# controller.net
KiCad netlist of a schematic drawn in Altium Designer
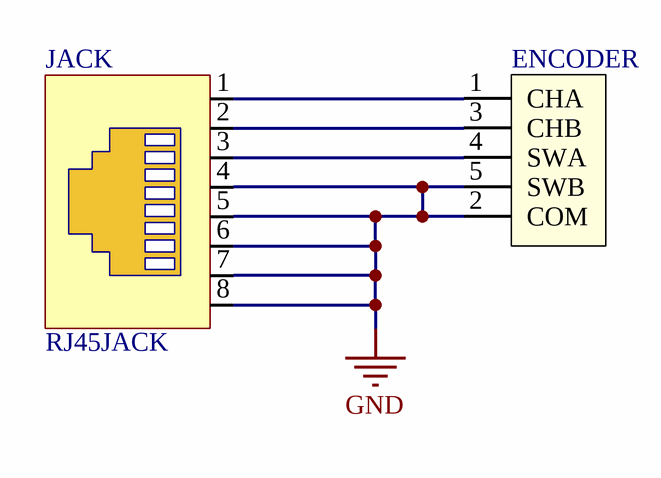
[diagram p0: controller.SchDoc]

(export (version "E")
  (design (tool "Eeschema 10.0.6"))
  (components
    (comp (ref "ENCODER")
      (value "ROTARY_ENCODER")
      (footprint "ENCODER")
      (description "Rotary Encoder")
      (libsource (lib "light_driver") (part "ROTARY_ENCODER"))
    )
    (comp (ref "JACK")
      (value "RJ45JACK")
      (footprint "RJHSE-5080")
      (libsource (lib "light_driver") (part "RJ45JACK"))
    )
  )
  (nets
    (net (code "1") (name "GND") (class "Default")
      (node (ref "ENCODER") (pin "2") (pinfunction "COM_2") (pintype "passive"))
      (node (ref "ENCODER") (pin "5") (pinfunction "SWB_5") (pintype "passive"))
      (node (ref "JACK") (pin "4") (pintype "passive"))
      (node (ref "JACK") (pin "5") (pintype "passive"))
      (node (ref "JACK") (pin "6") (pintype "passive"))
      (node (ref "JACK") (pin "7") (pintype "passive"))
      (node (ref "JACK") (pin "8") (pintype "passive"))
    )
    (net (code "2") (name "Net-(ENCODER-CHA)") (class "Default")
      (node (ref "ENCODER") (pin "1") (pinfunction "CHA_1") (pintype "passive"))
      (node (ref "JACK") (pin "1") (pintype "passive"))
    )
    (net (code "3") (name "Net-(ENCODER-CHB)") (class "Default")
      (node (ref "ENCODER") (pin "3") (pinfunction "CHB_3") (pintype "passive"))
      (node (ref "JACK") (pin "2") (pintype "passive"))
    )
    (net (code "4") (name "Net-(ENCODER-SWA)") (class "Default")
      (node (ref "ENCODER") (pin "4") (pinfunction "SWA_4") (pintype "passive"))
      (node (ref "JACK") (pin "3") (pintype "passive"))
    )
  )
)
